# Sheet1.net
KiCad netlist of a schematic drawn in Altium Designer
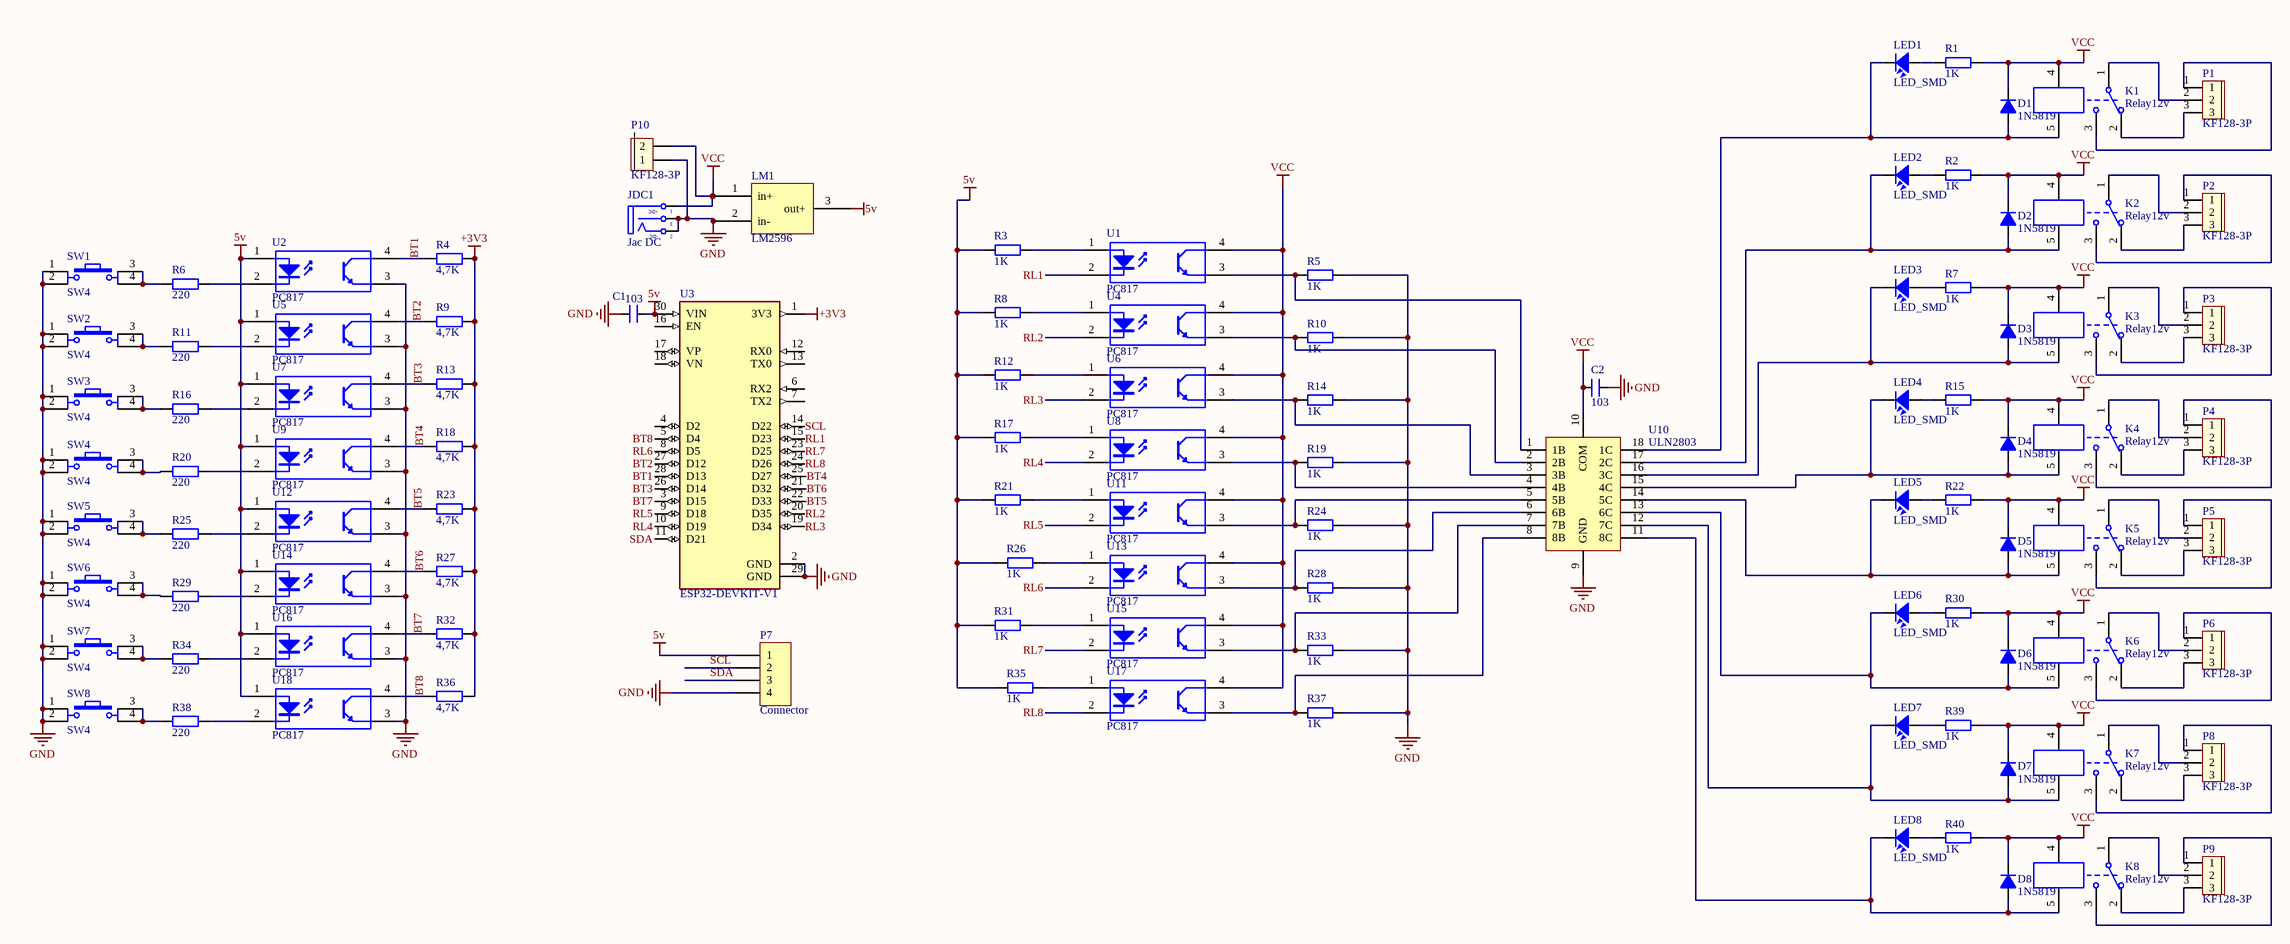
[diagram p0: Sheet1.SchDoc]

(export (version "E")
  (design (tool "Eeschema 10.0.6"))
  (components
    (comp (ref "C1")
      (value "103")
      (footprint "SM-1206")
      (description "Cap SMD")
      (libsource (lib "Schlib1") (part "CM"))
    )
    (comp (ref "C2")
      (value "103")
      (footprint "SM-1206")
      (description "Cap SMD")
      (libsource (lib "Schlib1") (part "CM"))
    )
    (comp (ref "D1") (value "1N5819") (footprint "diot_smd") (libsource (lib "Schlib1") (part "1N5819")))
    (comp (ref "D2") (value "1N5819") (footprint "diot_smd") (libsource (lib "Schlib1") (part "1N5819")))
    (comp (ref "D3") (value "1N5819") (footprint "diot_smd") (libsource (lib "Schlib1") (part "1N5819")))
    (comp (ref "D4") (value "1N5819") (footprint "diot_smd") (libsource (lib "Schlib1") (part "1N5819")))
    (comp (ref "D5") (value "1N5819") (footprint "diot_smd") (libsource (lib "Schlib1") (part "1N5819")))
    (comp (ref "D6") (value "1N5819") (footprint "diot_smd") (libsource (lib "Schlib1") (part "1N5819")))
    (comp (ref "D7") (value "1N5819") (footprint "diot_smd") (libsource (lib "Schlib1") (part "1N5819")))
    (comp (ref "D8") (value "1N5819") (footprint "diot_smd") (libsource (lib "Schlib1") (part "1N5819")))
    (comp (ref "JDC1")
      (value "Jac DC")
      (footprint "DC-IN")
      (description "Jac DC input")
      (libsource (lib "Schlib1") (part "DCIN"))
    )
    (comp (ref "K1")
      (value "Relay12v")
      (footprint "RELAY-10A5pin")
      (description "SRD-05VDC-SL-C1")
      (fields (field (name "PUBLISHER") "Altium Limited"))
      (libsource (lib "Schlib1") (part "Relay-SRD-05VDC-SL-C1"))
    )
    (comp (ref "K2")
      (value "Relay12v")
      (footprint "RELAY-10A5pin")
      (description "SRD-05VDC-SL-C1")
      (fields (field (name "PUBLISHER") "Altium Limited"))
      (libsource (lib "Schlib1") (part "Relay-SRD-05VDC-SL-C1"))
    )
    (comp (ref "K3")
      (value "Relay12v")
      (footprint "RELAY-10A5pin")
      (description "SRD-05VDC-SL-C1")
      (fields (field (name "PUBLISHER") "Altium Limited"))
      (libsource (lib "Schlib1") (part "Relay-SRD-05VDC-SL-C1"))
    )
    (comp (ref "K4")
      (value "Relay12v")
      (footprint "RELAY-10A5pin")
      (description "SRD-05VDC-SL-C1")
      (fields (field (name "PUBLISHER") "Altium Limited"))
      (libsource (lib "Schlib1") (part "Relay-SRD-05VDC-SL-C1"))
    )
    (comp (ref "K5")
      (value "Relay12v")
      (footprint "RELAY-10A5pin")
      (description "SRD-05VDC-SL-C1")
      (fields (field (name "PUBLISHER") "Altium Limited"))
      (libsource (lib "Schlib1") (part "Relay-SRD-05VDC-SL-C1"))
    )
    (comp (ref "K6")
      (value "Relay12v")
      (footprint "RELAY-10A5pin")
      (description "SRD-05VDC-SL-C1")
      (fields (field (name "PUBLISHER") "Altium Limited"))
      (libsource (lib "Schlib1") (part "Relay-SRD-05VDC-SL-C1"))
    )
    (comp (ref "K7")
      (value "Relay12v")
      (footprint "RELAY-10A5pin")
      (description "SRD-05VDC-SL-C1")
      (fields (field (name "PUBLISHER") "Altium Limited"))
      (libsource (lib "Schlib1") (part "Relay-SRD-05VDC-SL-C1"))
    )
    (comp (ref "K8")
      (value "Relay12v")
      (footprint "RELAY-10A5pin")
      (description "SRD-05VDC-SL-C1")
      (fields (field (name "PUBLISHER") "Altium Limited"))
      (libsource (lib "Schlib1") (part "Relay-SRD-05VDC-SL-C1"))
    )
    (comp (ref "LED1")
      (value "LED_SMD")
      (footprint "SM-LED-GEEN 1206")
      (libsource (lib "Schlib1") (part "LED_SMD"))
    )
    (comp (ref "LED2")
      (value "LED_SMD")
      (footprint "SM-LED-GEEN 1206")
      (libsource (lib "Schlib1") (part "LED_SMD"))
    )
    (comp (ref "LED3")
      (value "LED_SMD")
      (footprint "SM-LED-GEEN 1206")
      (libsource (lib "Schlib1") (part "LED_SMD"))
    )
    (comp (ref "LED4")
      (value "LED_SMD")
      (footprint "SM-LED-GEEN 1206")
      (libsource (lib "Schlib1") (part "LED_SMD"))
    )
    (comp (ref "LED5")
      (value "LED_SMD")
      (footprint "SM-LED-GEEN 1206")
      (libsource (lib "Schlib1") (part "LED_SMD"))
    )
    (comp (ref "LED6")
      (value "LED_SMD")
      (footprint "SM-LED-GEEN 1206")
      (libsource (lib "Schlib1") (part "LED_SMD"))
    )
    (comp (ref "LED7")
      (value "LED_SMD")
      (footprint "SM-LED-GEEN 1206")
      (libsource (lib "Schlib1") (part "LED_SMD"))
    )
    (comp (ref "LED8")
      (value "LED_SMD")
      (footprint "SM-LED-GEEN 1206")
      (libsource (lib "Schlib1") (part "LED_SMD"))
    )
    (comp (ref "LM1")
      (value "LM2596")
      (footprint "module2596_DUNG")
      (libsource (lib "Schlib1") (part "LM2596 module_dung"))
    )
    (comp (ref "P1")
      (value "KF128-3P")
      (footprint "con 3 kf128")
      (description "Cắm")
      (libsource (lib "Schlib1") (part "Con 3 KF128"))
    )
    (comp (ref "P2")
      (value "KF128-3P")
      (footprint "con 3 kf128")
      (description "Cắm")
      (libsource (lib "Schlib1") (part "Con 3 KF128"))
    )
    (comp (ref "P3")
      (value "KF128-3P")
      (footprint "con 3 kf128")
      (description "Cắm")
      (libsource (lib "Schlib1") (part "Con 3 KF128"))
    )
    (comp (ref "P4")
      (value "KF128-3P")
      (footprint "con 3 kf128")
      (description "Cắm")
      (libsource (lib "Schlib1") (part "Con 3 KF128"))
    )
    (comp (ref "P5")
      (value "KF128-3P")
      (footprint "con 3 kf128")
      (description "Cắm")
      (libsource (lib "Schlib1") (part "Con 3 KF128"))
    )
    (comp (ref "P6")
      (value "KF128-3P")
      (footprint "con 3 kf128")
      (description "Cắm")
      (libsource (lib "Schlib1") (part "Con 3 KF128"))
    )
    (comp (ref "P7")
      (value "Connector")
      (footprint "JST-XH_B4B-XH-A")
      (libsource (lib "Schlib1") (part "Connector_4pin"))
    )
    (comp (ref "P8")
      (value "KF128-3P")
      (footprint "con 3 kf128")
      (description "Cắm")
      (libsource (lib "Schlib1") (part "Con 3 KF128"))
    )
    (comp (ref "P9")
      (value "KF128-3P")
      (footprint "con 3 kf128")
      (description "Cắm")
      (libsource (lib "Schlib1") (part "Con 3 KF128"))
    )
    (comp (ref "P10")
      (value "KF128-3P")
      (footprint "con 2 kf128")
      (description "Cắm")
      (libsource (lib "Schlib1") (part "Con 2 KF128"))
    )
    (comp (ref "R1")
      (value "1K")
      (footprint "SM-1206")
      (description "Resistor SMD")
      (libsource (lib "Schlib1") (part "RM"))
    )
    (comp (ref "R2")
      (value "1K")
      (footprint "SM-1206")
      (description "Resistor SMD")
      (libsource (lib "Schlib1") (part "RM"))
    )
    (comp (ref "R3")
      (value "1K")
      (footprint "SM-1206")
      (description "Resistor SMD")
      (libsource (lib "Schlib1") (part "RM"))
    )
    (comp (ref "R4")
      (value "4,7K")
      (footprint "SM-1206")
      (description "Resistor SMD")
      (libsource (lib "Schlib1") (part "RM"))
    )
    (comp (ref "R5")
      (value "1K")
      (footprint "SM-1206")
      (description "Resistor SMD")
      (libsource (lib "Schlib1") (part "RM"))
    )
    (comp (ref "R6")
      (value "220")
      (footprint "SM-1206")
      (description "Resistor SMD")
      (libsource (lib "Schlib1") (part "RM"))
    )
    (comp (ref "R7")
      (value "1K")
      (footprint "SM-1206")
      (description "Resistor SMD")
      (libsource (lib "Schlib1") (part "RM"))
    )
    (comp (ref "R8")
      (value "1K")
      (footprint "SM-1206")
      (description "Resistor SMD")
      (libsource (lib "Schlib1") (part "RM"))
    )
    (comp (ref "R9")
      (value "4,7K")
      (footprint "SM-1206")
      (description "Resistor SMD")
      (libsource (lib "Schlib1") (part "RM"))
    )
    (comp (ref "R10")
      (value "1K")
      (footprint "SM-1206")
      (description "Resistor SMD")
      (libsource (lib "Schlib1") (part "RM"))
    )
    (comp (ref "R11")
      (value "220")
      (footprint "SM-1206")
      (description "Resistor SMD")
      (libsource (lib "Schlib1") (part "RM"))
    )
    (comp (ref "R12")
      (value "1K")
      (footprint "SM-1206")
      (description "Resistor SMD")
      (libsource (lib "Schlib1") (part "RM"))
    )
    (comp (ref "R13")
      (value "4,7K")
      (footprint "SM-1206")
      (description "Resistor SMD")
      (libsource (lib "Schlib1") (part "RM"))
    )
    (comp (ref "R14")
      (value "1K")
      (footprint "SM-1206")
      (description "Resistor SMD")
      (libsource (lib "Schlib1") (part "RM"))
    )
    (comp (ref "R15")
      (value "1K")
      (footprint "SM-1206")
      (description "Resistor SMD")
      (libsource (lib "Schlib1") (part "RM"))
    )
    (comp (ref "R16")
      (value "220")
      (footprint "SM-1206")
      (description "Resistor SMD")
      (libsource (lib "Schlib1") (part "RM"))
    )
    (comp (ref "R17")
      (value "1K")
      (footprint "SM-1206")
      (description "Resistor SMD")
      (libsource (lib "Schlib1") (part "RM"))
    )
    (comp (ref "R18")
      (value "4,7K")
      (footprint "SM-1206")
      (description "Resistor SMD")
      (libsource (lib "Schlib1") (part "RM"))
    )
    (comp (ref "R19")
      (value "1K")
      (footprint "SM-1206")
      (description "Resistor SMD")
      (libsource (lib "Schlib1") (part "RM"))
    )
    (comp (ref "R20")
      (value "220")
      (footprint "SM-1206")
      (description "Resistor SMD")
      (libsource (lib "Schlib1") (part "RM"))
    )
    (comp (ref "R21")
      (value "1K")
      (footprint "SM-1206")
      (description "Resistor SMD")
      (libsource (lib "Schlib1") (part "RM"))
    )
    (comp (ref "R22")
      (value "1K")
      (footprint "SM-1206")
      (description "Resistor SMD")
      (libsource (lib "Schlib1") (part "RM"))
    )
    (comp (ref "R23")
      (value "4,7K")
      (footprint "SM-1206")
      (description "Resistor SMD")
      (libsource (lib "Schlib1") (part "RM"))
    )
    (comp (ref "R24")
      (value "1K")
      (footprint "SM-1206")
      (description "Resistor SMD")
      (libsource (lib "Schlib1") (part "RM"))
    )
    (comp (ref "R25")
      (value "220")
      (footprint "SM-1206")
      (description "Resistor SMD")
      (libsource (lib "Schlib1") (part "RM"))
    )
    (comp (ref "R26")
      (value "1K")
      (footprint "SM-1206")
      (description "Resistor SMD")
      (libsource (lib "Schlib1") (part "RM"))
    )
    (comp (ref "R27")
      (value "4,7K")
      (footprint "SM-1206")
      (description "Resistor SMD")
      (libsource (lib "Schlib1") (part "RM"))
    )
    (comp (ref "R28")
      (value "1K")
      (footprint "SM-1206")
      (description "Resistor SMD")
      (libsource (lib "Schlib1") (part "RM"))
    )
    (comp (ref "R29")
      (value "220")
      (footprint "SM-1206")
      (description "Resistor SMD")
      (libsource (lib "Schlib1") (part "RM"))
    )
    (comp (ref "R30")
      (value "1K")
      (footprint "SM-1206")
      (description "Resistor SMD")
      (libsource (lib "Schlib1") (part "RM"))
    )
    (comp (ref "R31")
      (value "1K")
      (footprint "SM-1206")
      (description "Resistor SMD")
      (libsource (lib "Schlib1") (part "RM"))
    )
    (comp (ref "R32")
      (value "4,7K")
      (footprint "SM-1206")
      (description "Resistor SMD")
      (libsource (lib "Schlib1") (part "RM"))
    )
    (comp (ref "R33")
      (value "1K")
      (footprint "SM-1206")
      (description "Resistor SMD")
      (libsource (lib "Schlib1") (part "RM"))
    )
    (comp (ref "R34")
      (value "220")
      (footprint "SM-1206")
      (description "Resistor SMD")
      (libsource (lib "Schlib1") (part "RM"))
    )
    (comp (ref "R35")
      (value "1K")
      (footprint "SM-1206")
      (description "Resistor SMD")
      (libsource (lib "Schlib1") (part "RM"))
    )
    (comp (ref "R36")
      (value "4,7K")
      (footprint "SM-1206")
      (description "Resistor SMD")
      (libsource (lib "Schlib1") (part "RM"))
    )
    (comp (ref "R37")
      (value "1K")
      (footprint "SM-1206")
      (description "Resistor SMD")
      (libsource (lib "Schlib1") (part "RM"))
    )
    (comp (ref "R38")
      (value "220")
      (footprint "SM-1206")
      (description "Resistor SMD")
      (libsource (lib "Schlib1") (part "RM"))
    )
    (comp (ref "R39")
      (value "1K")
      (footprint "SM-1206")
      (description "Resistor SMD")
      (libsource (lib "Schlib1") (part "RM"))
    )
    (comp (ref "R40")
      (value "1K")
      (footprint "SM-1206")
      (description "Resistor SMD")
      (libsource (lib "Schlib1") (part "RM"))
    )
    (comp (ref "SW1")
      (value "SW4")
      (footprint "SW4")
      (description "Switch button 4 pin")
      (libsource (lib "Schlib1") (part "SW4"))
    )
    (comp (ref "SW2")
      (value "SW4")
      (footprint "SW4")
      (description "Switch button 4 pin")
      (libsource (lib "Schlib1") (part "SW4"))
    )
    (comp (ref "SW3")
      (value "SW4")
      (footprint "SW4")
      (description "Switch button 4 pin")
      (libsource (lib "Schlib1") (part "SW4"))
    )
    (comp (ref "SW4")
      (value "SW4")
      (footprint "SW4")
      (description "Switch button 4 pin")
      (libsource (lib "Schlib1") (part "SW4"))
    )
    (comp (ref "SW5")
      (value "SW4")
      (footprint "SW4")
      (description "Switch button 4 pin")
      (libsource (lib "Schlib1") (part "SW4"))
    )
    (comp (ref "SW6")
      (value "SW4")
      (footprint "SW4")
      (description "Switch button 4 pin")
      (libsource (lib "Schlib1") (part "SW4"))
    )
    (comp (ref "SW7")
      (value "SW4")
      (footprint "SW4")
      (description "Switch button 4 pin")
      (libsource (lib "Schlib1") (part "SW4"))
    )
    (comp (ref "SW8")
      (value "SW4")
      (footprint "SW4")
      (description "Switch button 4 pin")
      (libsource (lib "Schlib1") (part "SW4"))
    )
    (comp (ref "U1")
      (value "PC817")
      (footprint "PhotoCoupler_SMD")
      (description "4-Pin Phototransistor Optocoupler")
      (fields (field (name "PUBLISHER") "Altium Limited"))
      (libsource (lib "Schlib1") (part "PC817"))
    )
    (comp (ref "U2")
      (value "PC817")
      (footprint "PhotoCoupler_SMD")
      (description "4-Pin Phototransistor Optocoupler")
      (fields (field (name "PUBLISHER") "Altium Limited"))
      (libsource (lib "Schlib1") (part "PC817"))
    )
    (comp (ref "U3")
      (value "ESP32-DEVKIT-V1")
      (footprint "MODULE_ESP32_DEVKIT_V1")
      (fields (field (name "MF") "Do it"))
      (libsource (lib "Schlib1") (part "ESP32-DEVKIT-V1"))
    )
    (comp (ref "U4")
      (value "PC817")
      (footprint "PhotoCoupler_SMD")
      (description "4-Pin Phototransistor Optocoupler")
      (fields (field (name "PUBLISHER") "Altium Limited"))
      (libsource (lib "Schlib1") (part "PC817"))
    )
    (comp (ref "U5")
      (value "PC817")
      (footprint "PhotoCoupler_SMD")
      (description "4-Pin Phototransistor Optocoupler")
      (fields (field (name "PUBLISHER") "Altium Limited"))
      (libsource (lib "Schlib1") (part "PC817"))
    )
    (comp (ref "U6")
      (value "PC817")
      (footprint "PhotoCoupler_SMD")
      (description "4-Pin Phototransistor Optocoupler")
      (fields (field (name "PUBLISHER") "Altium Limited"))
      (libsource (lib "Schlib1") (part "PC817"))
    )
    (comp (ref "U7")
      (value "PC817")
      (footprint "PhotoCoupler_SMD")
      (description "4-Pin Phototransistor Optocoupler")
      (fields (field (name "PUBLISHER") "Altium Limited"))
      (libsource (lib "Schlib1") (part "PC817"))
    )
    (comp (ref "U8")
      (value "PC817")
      (footprint "PhotoCoupler_SMD")
      (description "4-Pin Phototransistor Optocoupler")
      (fields (field (name "PUBLISHER") "Altium Limited"))
      (libsource (lib "Schlib1") (part "PC817"))
    )
    (comp (ref "U9")
      (value "PC817")
      (footprint "PhotoCoupler_SMD")
      (description "4-Pin Phototransistor Optocoupler")
      (fields (field (name "PUBLISHER") "Altium Limited"))
      (libsource (lib "Schlib1") (part "PC817"))
    )
    (comp (ref "U10")
      (value "ULN2803")
      (footprint "SO-18")
      (description "ULN2803A Darlington Transistor Arrays")
      (libsource (lib "Schlib1") (part "ULN2803"))
    )
    (comp (ref "U11")
      (value "PC817")
      (footprint "PhotoCoupler_SMD")
      (description "4-Pin Phototransistor Optocoupler")
      (fields (field (name "PUBLISHER") "Altium Limited"))
      (libsource (lib "Schlib1") (part "PC817"))
    )
    (comp (ref "U12")
      (value "PC817")
      (footprint "PhotoCoupler_SMD")
      (description "4-Pin Phototransistor Optocoupler")
      (fields (field (name "PUBLISHER") "Altium Limited"))
      (libsource (lib "Schlib1") (part "PC817"))
    )
    (comp (ref "U13")
      (value "PC817")
      (footprint "PhotoCoupler_SMD")
      (description "4-Pin Phototransistor Optocoupler")
      (fields (field (name "PUBLISHER") "Altium Limited"))
      (libsource (lib "Schlib1") (part "PC817"))
    )
    (comp (ref "U14")
      (value "PC817")
      (footprint "PhotoCoupler_SMD")
      (description "4-Pin Phototransistor Optocoupler")
      (fields (field (name "PUBLISHER") "Altium Limited"))
      (libsource (lib "Schlib1") (part "PC817"))
    )
    (comp (ref "U15")
      (value "PC817")
      (footprint "PhotoCoupler_SMD")
      (description "4-Pin Phototransistor Optocoupler")
      (fields (field (name "PUBLISHER") "Altium Limited"))
      (libsource (lib "Schlib1") (part "PC817"))
    )
    (comp (ref "U16")
      (value "PC817")
      (footprint "PhotoCoupler_SMD")
      (description "4-Pin Phototransistor Optocoupler")
      (fields (field (name "PUBLISHER") "Altium Limited"))
      (libsource (lib "Schlib1") (part "PC817"))
    )
    (comp (ref "U17")
      (value "PC817")
      (footprint "PhotoCoupler_SMD")
      (description "4-Pin Phototransistor Optocoupler")
      (fields (field (name "PUBLISHER") "Altium Limited"))
      (libsource (lib "Schlib1") (part "PC817"))
    )
    (comp (ref "U18")
      (value "PC817")
      (footprint "PhotoCoupler_SMD")
      (description "4-Pin Phototransistor Optocoupler")
      (fields (field (name "PUBLISHER") "Altium Limited"))
      (libsource (lib "Schlib1") (part "PC817"))
    )
  )
  (nets
    (net (code "1") (name "+3V3") (class "Default")
      (node (ref "R13") (pin "2") (pinfunction "2_2") (pintype "passive"))
      (node (ref "R18") (pin "2") (pinfunction "2_2") (pintype "passive"))
      (node (ref "R23") (pin "2") (pinfunction "2_2") (pintype "passive"))
      (node (ref "R27") (pin "2") (pinfunction "2_2") (pintype "passive"))
      (node (ref "R32") (pin "2") (pinfunction "2_2") (pintype "passive"))
      (node (ref "R36") (pin "2") (pinfunction "2_2") (pintype "passive"))
      (node (ref "R4") (pin "2") (pinfunction "2_2") (pintype "passive"))
      (node (ref "R9") (pin "2") (pinfunction "2_2") (pintype "passive"))
      (node (ref "U3") (pin "1") (pinfunction "3V3_1") (pintype "output"))
    )
    (net (code "2") (name "/BT1") (class "Default")
      (node (ref "R4") (pin "1") (pinfunction "1_1") (pintype "passive"))
      (node (ref "U2") (pin "4") (pinfunction "C_4") (pintype "passive"))
      (node (ref "U3") (pin "28") (pinfunction "D13_28") (pintype "bidirectional"))
    )
    (net (code "3") (name "/BT2") (class "Default")
      (node (ref "R9") (pin "1") (pinfunction "1_1") (pintype "passive"))
      (node (ref "U3") (pin "27") (pinfunction "D12_27") (pintype "bidirectional"))
      (node (ref "U5") (pin "4") (pinfunction "C_4") (pintype "passive"))
    )
    (net (code "4") (name "/BT3") (class "Default")
      (node (ref "R13") (pin "1") (pinfunction "1_1") (pintype "passive"))
      (node (ref "U3") (pin "26") (pinfunction "D14_26") (pintype "bidirectional"))
      (node (ref "U7") (pin "4") (pinfunction "C_4") (pintype "passive"))
    )
    (net (code "5") (name "/BT4") (class "Default")
      (node (ref "R18") (pin "1") (pinfunction "1_1") (pintype "passive"))
      (node (ref "U3") (pin "25") (pinfunction "D27_25") (pintype "bidirectional"))
      (node (ref "U9") (pin "4") (pinfunction "C_4") (pintype "passive"))
    )
    (net (code "6") (name "/BT5") (class "Default")
      (node (ref "R23") (pin "1") (pinfunction "1_1") (pintype "passive"))
      (node (ref "U12") (pin "4") (pinfunction "C_4") (pintype "passive"))
      (node (ref "U3") (pin "22") (pinfunction "D33_22") (pintype "bidirectional"))
    )
    (net (code "7") (name "/BT6") (class "Default")
      (node (ref "R27") (pin "1") (pinfunction "1_1") (pintype "passive"))
      (node (ref "U14") (pin "4") (pinfunction "C_4") (pintype "passive"))
      (node (ref "U3") (pin "21") (pinfunction "D32_21") (pintype "bidirectional"))
    )
    (net (code "8") (name "/BT7") (class "Default")
      (node (ref "R32") (pin "1") (pinfunction "1_1") (pintype "passive"))
      (node (ref "U16") (pin "4") (pinfunction "C_4") (pintype "passive"))
      (node (ref "U3") (pin "3") (pinfunction "D15_3") (pintype "bidirectional"))
    )
    (net (code "9") (name "/BT8") (class "Default")
      (node (ref "R36") (pin "1") (pinfunction "1_1") (pintype "passive"))
      (node (ref "U18") (pin "4") (pinfunction "C_4") (pintype "passive"))
      (node (ref "U3") (pin "5") (pinfunction "D4_5") (pintype "bidirectional"))
    )
    (net (code "10") (name "/RL1") (class "Default")
      (node (ref "U1") (pin "2") (pinfunction "K_2") (pintype "passive"))
      (node (ref "U3") (pin "15") (pinfunction "D23_15") (pintype "bidirectional"))
    )
    (net (code "11") (name "/RL2") (class "Default")
      (node (ref "U3") (pin "20") (pinfunction "D35_20") (pintype "bidirectional"))
      (node (ref "U4") (pin "2") (pinfunction "K_2") (pintype "passive"))
    )
    (net (code "12") (name "/RL3") (class "Default")
      (node (ref "U3") (pin "19") (pinfunction "D34_19") (pintype "bidirectional"))
      (node (ref "U6") (pin "2") (pinfunction "K_2") (pintype "passive"))
    )
    (net (code "13") (name "/RL4") (class "Default")
      (node (ref "U3") (pin "10") (pinfunction "D19_10") (pintype "bidirectional"))
      (node (ref "U8") (pin "2") (pinfunction "K_2") (pintype "passive"))
    )
    (net (code "14") (name "/RL5") (class "Default")
      (node (ref "U11") (pin "2") (pinfunction "K_2") (pintype "passive"))
      (node (ref "U3") (pin "9") (pinfunction "D18_9") (pintype "bidirectional"))
    )
    (net (code "15") (name "/RL6") (class "Default")
      (node (ref "U13") (pin "2") (pinfunction "K_2") (pintype "passive"))
      (node (ref "U3") (pin "8") (pinfunction "D5_8") (pintype "bidirectional"))
    )
    (net (code "16") (name "/RL7") (class "Default")
      (node (ref "U15") (pin "2") (pinfunction "K_2") (pintype "passive"))
      (node (ref "U3") (pin "23") (pinfunction "D25_23") (pintype "bidirectional"))
    )
    (net (code "17") (name "/RL8") (class "Default")
      (node (ref "U17") (pin "2") (pinfunction "K_2") (pintype "passive"))
      (node (ref "U3") (pin "24") (pinfunction "D26_24") (pintype "bidirectional"))
    )
    (net (code "18") (name "/SCL") (class "Default")
      (node (ref "P7") (pin "2") (pinfunction "2_2") (pintype "passive"))
      (node (ref "U3") (pin "14") (pinfunction "D22_14") (pintype "bidirectional"))
    )
    (net (code "19") (name "/SDA") (class "Default")
      (node (ref "P7") (pin "3") (pinfunction "3_3") (pintype "passive"))
      (node (ref "U3") (pin "11") (pinfunction "D21_11") (pintype "bidirectional"))
    )
    (net (code "20") (name "5v") (class "Default")
      (node (ref "C1") (pin "1") (pinfunction "1_1") (pintype "passive"))
      (node (ref "LM1") (pin "3") (pinfunction "out+_3") (pintype "passive"))
      (node (ref "P7") (pin "1") (pinfunction "1_1") (pintype "passive"))
      (node (ref "R12") (pin "1") (pinfunction "1_1") (pintype "passive"))
      (node (ref "R17") (pin "1") (pinfunction "1_1") (pintype "passive"))
      (node (ref "R21") (pin "1") (pinfunction "1_1") (pintype "passive"))
      (node (ref "R26") (pin "1") (pinfunction "1_1") (pintype "passive"))
      (node (ref "R3") (pin "1") (pinfunction "1_1") (pintype "passive"))
      (node (ref "R31") (pin "1") (pinfunction "1_1") (pintype "passive"))
      (node (ref "R35") (pin "1") (pinfunction "1_1") (pintype "passive"))
      (node (ref "R8") (pin "1") (pinfunction "1_1") (pintype "passive"))
      (node (ref "U12") (pin "1") (pinfunction "A_1") (pintype "passive"))
      (node (ref "U14") (pin "1") (pinfunction "A_1") (pintype "passive"))
      (node (ref "U16") (pin "1") (pinfunction "A_1") (pintype "passive"))
      (node (ref "U18") (pin "1") (pinfunction "A_1") (pintype "passive"))
      (node (ref "U2") (pin "1") (pinfunction "A_1") (pintype "passive"))
      (node (ref "U3") (pin "30") (pinfunction "VIN_30") (pintype "input"))
      (node (ref "U5") (pin "1") (pinfunction "A_1") (pintype "passive"))
      (node (ref "U7") (pin "1") (pinfunction "A_1") (pintype "passive"))
      (node (ref "U9") (pin "1") (pinfunction "A_1") (pintype "passive"))
    )
    (net (code "21") (name "GND") (class "Default")
      (node (ref "C1") (pin "2") (pinfunction "2_2") (pintype "passive"))
      (node (ref "C2") (pin "1") (pinfunction "1_1") (pintype "passive"))
      (node (ref "JDC1") (pin "2") (pinfunction "TN_2") (pintype "passive"))
      (node (ref "JDC1") (pin "3") (pinfunction "S_3") (pintype "power_in"))
      (node (ref "LM1") (pin "2") (pinfunction "in-_2") (pintype "passive"))
      (node (ref "P10") (pin "1") (pinfunction "1_1") (pintype "passive"))
      (node (ref "P7") (pin "4") (pinfunction "4_4") (pintype "passive"))
      (node (ref "R10") (pin "2") (pinfunction "2_2") (pintype "passive"))
      (node (ref "R14") (pin "2") (pinfunction "2_2") (pintype "passive"))
      (node (ref "R19") (pin "2") (pinfunction "2_2") (pintype "passive"))
      (node (ref "R24") (pin "2") (pinfunction "2_2") (pintype "passive"))
      (node (ref "R28") (pin "2") (pinfunction "2_2") (pintype "passive"))
      (node (ref "R33") (pin "2") (pinfunction "2_2") (pintype "passive"))
      (node (ref "R37") (pin "2") (pinfunction "2_2") (pintype "passive"))
      (node (ref "R5") (pin "2") (pinfunction "2_2") (pintype "passive"))
      (node (ref "SW1") (pin "1") (pintype "passive"))
      (node (ref "SW1") (pin "2") (pintype "passive"))
      (node (ref "SW2") (pin "1") (pintype "passive"))
      (node (ref "SW2") (pin "2") (pintype "passive"))
      (node (ref "SW3") (pin "1") (pintype "passive"))
      (node (ref "SW3") (pin "2") (pintype "passive"))
      (node (ref "SW4") (pin "1") (pintype "passive"))
      (node (ref "SW4") (pin "2") (pintype "passive"))
      (node (ref "SW5") (pin "1") (pintype "passive"))
      (node (ref "SW5") (pin "2") (pintype "passive"))
      (node (ref "SW6") (pin "1") (pintype "passive"))
      (node (ref "SW6") (pin "2") (pintype "passive"))
      (node (ref "SW7") (pin "1") (pintype "passive"))
      (node (ref "SW7") (pin "2") (pintype "passive"))
      (node (ref "SW8") (pin "1") (pintype "passive"))
      (node (ref "SW8") (pin "2") (pintype "passive"))
      (node (ref "U10") (pin "9") (pinfunction "GND_9") (pintype "passive"))
      (node (ref "U12") (pin "3") (pinfunction "E_3") (pintype "passive"))
      (node (ref "U14") (pin "3") (pinfunction "E_3") (pintype "passive"))
      (node (ref "U16") (pin "3") (pinfunction "E_3") (pintype "passive"))
      (node (ref "U18") (pin "3") (pinfunction "E_3") (pintype "passive"))
      (node (ref "U2") (pin "3") (pinfunction "E_3") (pintype "passive"))
      (node (ref "U3") (pin "2") (pinfunction "GND_2") (pintype "power_in"))
      (node (ref "U3") (pin "29") (pinfunction "GND_29") (pintype "power_in"))
      (node (ref "U5") (pin "3") (pinfunction "E_3") (pintype "passive"))
      (node (ref "U7") (pin "3") (pinfunction "E_3") (pintype "passive"))
      (node (ref "U9") (pin "3") (pinfunction "E_3") (pintype "passive"))
    )
    (net (code "22") (name "Net-(D1-A)") (class "Default")
      (node (ref "D1") (pin "1") (pinfunction "A_1") (pintype "passive"))
      (node (ref "K1") (pin "5") (pintype "passive"))
      (node (ref "LED1") (pin "2") (pinfunction "2_2") (pintype "passive"))
      (node (ref "U10") (pin "18") (pinfunction "1C_18") (pintype "passive"))
    )
    (net (code "23") (name "Net-(D2-A)") (class "Default")
      (node (ref "D2") (pin "1") (pinfunction "A_1") (pintype "passive"))
      (node (ref "K2") (pin "5") (pintype "passive"))
      (node (ref "LED2") (pin "2") (pinfunction "2_2") (pintype "passive"))
      (node (ref "U10") (pin "17") (pinfunction "2C_17") (pintype "passive"))
    )
    (net (code "24") (name "Net-(D3-A)") (class "Default")
      (node (ref "D3") (pin "1") (pinfunction "A_1") (pintype "passive"))
      (node (ref "K3") (pin "5") (pintype "passive"))
      (node (ref "LED3") (pin "2") (pinfunction "2_2") (pintype "passive"))
      (node (ref "U10") (pin "16") (pinfunction "3C_16") (pintype "passive"))
    )
    (net (code "25") (name "Net-(D4-A)") (class "Default")
      (node (ref "D4") (pin "1") (pinfunction "A_1") (pintype "passive"))
      (node (ref "K4") (pin "5") (pintype "passive"))
      (node (ref "LED4") (pin "2") (pinfunction "2_2") (pintype "passive"))
      (node (ref "U10") (pin "15") (pinfunction "4C_15") (pintype "passive"))
    )
    (net (code "26") (name "Net-(D5-A)") (class "Default")
      (node (ref "D5") (pin "1") (pinfunction "A_1") (pintype "passive"))
      (node (ref "K5") (pin "5") (pintype "passive"))
      (node (ref "LED5") (pin "2") (pinfunction "2_2") (pintype "passive"))
      (node (ref "U10") (pin "14") (pinfunction "5C_14") (pintype "passive"))
    )
    (net (code "27") (name "Net-(D6-A)") (class "Default")
      (node (ref "D6") (pin "1") (pinfunction "A_1") (pintype "passive"))
      (node (ref "K6") (pin "5") (pintype "passive"))
      (node (ref "LED6") (pin "2") (pinfunction "2_2") (pintype "passive"))
      (node (ref "U10") (pin "13") (pinfunction "6C_13") (pintype "passive"))
    )
    (net (code "28") (name "Net-(D7-A)") (class "Default")
      (node (ref "D7") (pin "1") (pinfunction "A_1") (pintype "passive"))
      (node (ref "K7") (pin "5") (pintype "passive"))
      (node (ref "LED7") (pin "2") (pinfunction "2_2") (pintype "passive"))
      (node (ref "U10") (pin "12") (pinfunction "7C_12") (pintype "passive"))
    )
    (net (code "29") (name "Net-(D8-A)") (class "Default")
      (node (ref "D8") (pin "1") (pinfunction "A_1") (pintype "passive"))
      (node (ref "K8") (pin "5") (pintype "passive"))
      (node (ref "LED8") (pin "2") (pinfunction "2_2") (pintype "passive"))
      (node (ref "U10") (pin "11") (pinfunction "8C_11") (pintype "passive"))
    )
    (net (code "30") (name "Net-(K1-COM)") (class "Default")
      (node (ref "K1") (pin "1") (pinfunction "COM_1") (pintype "passive"))
      (node (ref "P1") (pin "2") (pinfunction "2_2") (pintype "passive"))
    )
    (net (code "31") (name "Net-(K1-NC)") (class "Default")
      (node (ref "K1") (pin "2") (pinfunction "NC_2") (pintype "passive"))
      (node (ref "P1") (pin "3") (pinfunction "3_3") (pintype "passive"))
    )
    (net (code "32") (name "Net-(K1-NO)") (class "Default")
      (node (ref "K1") (pin "3") (pinfunction "NO_3") (pintype "passive"))
      (node (ref "P1") (pin "1") (pinfunction "1_1") (pintype "passive"))
    )
    (net (code "33") (name "Net-(K2-COM)") (class "Default")
      (node (ref "K2") (pin "1") (pinfunction "COM_1") (pintype "passive"))
      (node (ref "P2") (pin "2") (pinfunction "2_2") (pintype "passive"))
    )
    (net (code "34") (name "Net-(K2-NC)") (class "Default")
      (node (ref "K2") (pin "2") (pinfunction "NC_2") (pintype "passive"))
      (node (ref "P2") (pin "3") (pinfunction "3_3") (pintype "passive"))
    )
    (net (code "35") (name "Net-(K2-NO)") (class "Default")
      (node (ref "K2") (pin "3") (pinfunction "NO_3") (pintype "passive"))
      (node (ref "P2") (pin "1") (pinfunction "1_1") (pintype "passive"))
    )
    (net (code "36") (name "Net-(K3-COM)") (class "Default")
      (node (ref "K3") (pin "1") (pinfunction "COM_1") (pintype "passive"))
      (node (ref "P3") (pin "2") (pinfunction "2_2") (pintype "passive"))
    )
    (net (code "37") (name "Net-(K3-NC)") (class "Default")
      (node (ref "K3") (pin "2") (pinfunction "NC_2") (pintype "passive"))
      (node (ref "P3") (pin "3") (pinfunction "3_3") (pintype "passive"))
    )
    (net (code "38") (name "Net-(K3-NO)") (class "Default")
      (node (ref "K3") (pin "3") (pinfunction "NO_3") (pintype "passive"))
      (node (ref "P3") (pin "1") (pinfunction "1_1") (pintype "passive"))
    )
    (net (code "39") (name "Net-(K4-COM)") (class "Default")
      (node (ref "K4") (pin "1") (pinfunction "COM_1") (pintype "passive"))
      (node (ref "P4") (pin "2") (pinfunction "2_2") (pintype "passive"))
    )
    (net (code "40") (name "Net-(K4-NC)") (class "Default")
      (node (ref "K4") (pin "2") (pinfunction "NC_2") (pintype "passive"))
      (node (ref "P4") (pin "3") (pinfunction "3_3") (pintype "passive"))
    )
    (net (code "41") (name "Net-(K4-NO)") (class "Default")
      (node (ref "K4") (pin "3") (pinfunction "NO_3") (pintype "passive"))
      (node (ref "P4") (pin "1") (pinfunction "1_1") (pintype "passive"))
    )
    (net (code "42") (name "Net-(K5-COM)") (class "Default")
      (node (ref "K5") (pin "1") (pinfunction "COM_1") (pintype "passive"))
      (node (ref "P5") (pin "2") (pinfunction "2_2") (pintype "passive"))
    )
    (net (code "43") (name "Net-(K5-NC)") (class "Default")
      (node (ref "K5") (pin "2") (pinfunction "NC_2") (pintype "passive"))
      (node (ref "P5") (pin "3") (pinfunction "3_3") (pintype "passive"))
    )
    (net (code "44") (name "Net-(K5-NO)") (class "Default")
      (node (ref "K5") (pin "3") (pinfunction "NO_3") (pintype "passive"))
      (node (ref "P5") (pin "1") (pinfunction "1_1") (pintype "passive"))
    )
    (net (code "45") (name "Net-(K6-COM)") (class "Default")
      (node (ref "K6") (pin "1") (pinfunction "COM_1") (pintype "passive"))
      (node (ref "P6") (pin "2") (pinfunction "2_2") (pintype "passive"))
    )
    (net (code "46") (name "Net-(K6-NC)") (class "Default")
      (node (ref "K6") (pin "2") (pinfunction "NC_2") (pintype "passive"))
      (node (ref "P6") (pin "3") (pinfunction "3_3") (pintype "passive"))
    )
    (net (code "47") (name "Net-(K6-NO)") (class "Default")
      (node (ref "K6") (pin "3") (pinfunction "NO_3") (pintype "passive"))
      (node (ref "P6") (pin "1") (pinfunction "1_1") (pintype "passive"))
    )
    (net (code "48") (name "Net-(K7-COM)") (class "Default")
      (node (ref "K7") (pin "1") (pinfunction "COM_1") (pintype "passive"))
      (node (ref "P8") (pin "2") (pinfunction "2_2") (pintype "passive"))
    )
    (net (code "49") (name "Net-(K7-NC)") (class "Default")
      (node (ref "K7") (pin "2") (pinfunction "NC_2") (pintype "passive"))
      (node (ref "P8") (pin "3") (pinfunction "3_3") (pintype "passive"))
    )
    (net (code "50") (name "Net-(K7-NO)") (class "Default")
      (node (ref "K7") (pin "3") (pinfunction "NO_3") (pintype "passive"))
      (node (ref "P8") (pin "1") (pinfunction "1_1") (pintype "passive"))
    )
    (net (code "51") (name "Net-(K8-COM)") (class "Default")
      (node (ref "K8") (pin "1") (pinfunction "COM_1") (pintype "passive"))
      (node (ref "P9") (pin "2") (pinfunction "2_2") (pintype "passive"))
    )
    (net (code "52") (name "Net-(K8-NC)") (class "Default")
      (node (ref "K8") (pin "2") (pinfunction "NC_2") (pintype "passive"))
      (node (ref "P9") (pin "3") (pinfunction "3_3") (pintype "passive"))
    )
    (net (code "53") (name "Net-(K8-NO)") (class "Default")
      (node (ref "K8") (pin "3") (pinfunction "NO_3") (pintype "passive"))
      (node (ref "P9") (pin "1") (pinfunction "1_1") (pintype "passive"))
    )
    (net (code "54") (name "Net-(LED1-Pad1)") (class "Default")
      (node (ref "LED1") (pin "1") (pinfunction "1_1") (pintype "passive"))
      (node (ref "R1") (pin "1") (pinfunction "1_1") (pintype "passive"))
    )
    (net (code "55") (name "Net-(LED2-Pad1)") (class "Default")
      (node (ref "LED2") (pin "1") (pinfunction "1_1") (pintype "passive"))
      (node (ref "R2") (pin "1") (pinfunction "1_1") (pintype "passive"))
    )
    (net (code "56") (name "Net-(LED3-Pad1)") (class "Default")
      (node (ref "LED3") (pin "1") (pinfunction "1_1") (pintype "passive"))
      (node (ref "R7") (pin "1") (pinfunction "1_1") (pintype "passive"))
    )
    (net (code "57") (name "Net-(LED4-Pad1)") (class "Default")
      (node (ref "LED4") (pin "1") (pinfunction "1_1") (pintype "passive"))
      (node (ref "R15") (pin "1") (pinfunction "1_1") (pintype "passive"))
    )
    (net (code "58") (name "Net-(LED5-Pad1)") (class "Default")
      (node (ref "LED5") (pin "1") (pinfunction "1_1") (pintype "passive"))
      (node (ref "R22") (pin "1") (pinfunction "1_1") (pintype "passive"))
    )
    (net (code "59") (name "Net-(LED6-Pad1)") (class "Default")
      (node (ref "LED6") (pin "1") (pinfunction "1_1") (pintype "passive"))
      (node (ref "R30") (pin "1") (pinfunction "1_1") (pintype "passive"))
    )
    (net (code "60") (name "Net-(LED7-Pad1)") (class "Default")
      (node (ref "LED7") (pin "1") (pinfunction "1_1") (pintype "passive"))
      (node (ref "R39") (pin "1") (pinfunction "1_1") (pintype "passive"))
    )
    (net (code "61") (name "Net-(LED8-Pad1)") (class "Default")
      (node (ref "LED8") (pin "1") (pinfunction "1_1") (pintype "passive"))
      (node (ref "R40") (pin "1") (pinfunction "1_1") (pintype "passive"))
    )
    (net (code "62") (name "Net-(R6-Pad1)") (class "Default")
      (node (ref "R6") (pin "1") (pinfunction "1_1") (pintype "passive"))
      (node (ref "SW1") (pin "3") (pintype "passive"))
      (node (ref "SW1") (pin "4") (pintype "passive"))
    )
    (net (code "63") (name "Net-(R11-Pad1)") (class "Default")
      (node (ref "R11") (pin "1") (pinfunction "1_1") (pintype "passive"))
      (node (ref "SW2") (pin "3") (pintype "passive"))
      (node (ref "SW2") (pin "4") (pintype "passive"))
    )
    (net (code "64") (name "Net-(R16-Pad1)") (class "Default")
      (node (ref "R16") (pin "1") (pinfunction "1_1") (pintype "passive"))
      (node (ref "SW3") (pin "3") (pintype "passive"))
      (node (ref "SW3") (pin "4") (pintype "passive"))
    )
    (net (code "65") (name "Net-(R20-Pad1)") (class "Default")
      (node (ref "R20") (pin "1") (pinfunction "1_1") (pintype "passive"))
      (node (ref "SW4") (pin "3") (pintype "passive"))
      (node (ref "SW4") (pin "4") (pintype "passive"))
    )
    (net (code "66") (name "Net-(R25-Pad1)") (class "Default")
      (node (ref "R25") (pin "1") (pinfunction "1_1") (pintype "passive"))
      (node (ref "SW5") (pin "3") (pintype "passive"))
      (node (ref "SW5") (pin "4") (pintype "passive"))
    )
    (net (code "67") (name "Net-(R29-Pad1)") (class "Default")
      (node (ref "R29") (pin "1") (pinfunction "1_1") (pintype "passive"))
      (node (ref "SW6") (pin "3") (pintype "passive"))
      (node (ref "SW6") (pin "4") (pintype "passive"))
    )
    (net (code "68") (name "Net-(R34-Pad1)") (class "Default")
      (node (ref "R34") (pin "1") (pinfunction "1_1") (pintype "passive"))
      (node (ref "SW7") (pin "3") (pintype "passive"))
      (node (ref "SW7") (pin "4") (pintype "passive"))
    )
    (net (code "69") (name "Net-(R38-Pad1)") (class "Default")
      (node (ref "R38") (pin "1") (pinfunction "1_1") (pintype "passive"))
      (node (ref "SW8") (pin "3") (pintype "passive"))
      (node (ref "SW8") (pin "4") (pintype "passive"))
    )
    (net (code "70") (name "Net-(U1-A)") (class "Default")
      (node (ref "R3") (pin "2") (pinfunction "2_2") (pintype "passive"))
      (node (ref "U1") (pin "1") (pinfunction "A_1") (pintype "passive"))
    )
    (net (code "71") (name "Net-(U1-E)") (class "Default")
      (node (ref "R5") (pin "1") (pinfunction "1_1") (pintype "passive"))
      (node (ref "U1") (pin "3") (pinfunction "E_3") (pintype "passive"))
      (node (ref "U10") (pin "1") (pinfunction "1B_1") (pintype "passive"))
    )
    (net (code "72") (name "Net-(U2-K)") (class "Default")
      (node (ref "R6") (pin "2") (pinfunction "2_2") (pintype "passive"))
      (node (ref "U2") (pin "2") (pinfunction "K_2") (pintype "passive"))
    )
    (net (code "73") (name "Net-(U4-A)") (class "Default")
      (node (ref "R8") (pin "2") (pinfunction "2_2") (pintype "passive"))
      (node (ref "U4") (pin "1") (pinfunction "A_1") (pintype "passive"))
    )
    (net (code "74") (name "Net-(U5-K)") (class "Default")
      (node (ref "R11") (pin "2") (pinfunction "2_2") (pintype "passive"))
      (node (ref "U5") (pin "2") (pinfunction "K_2") (pintype "passive"))
    )
    (net (code "75") (name "Net-(U6-A)") (class "Default")
      (node (ref "R12") (pin "2") (pinfunction "2_2") (pintype "passive"))
      (node (ref "U6") (pin "1") (pinfunction "A_1") (pintype "passive"))
    )
    (net (code "76") (name "Net-(U7-K)") (class "Default")
      (node (ref "R16") (pin "2") (pinfunction "2_2") (pintype "passive"))
      (node (ref "U7") (pin "2") (pinfunction "K_2") (pintype "passive"))
    )
    (net (code "77") (name "Net-(U8-A)") (class "Default")
      (node (ref "R17") (pin "2") (pinfunction "2_2") (pintype "passive"))
      (node (ref "U8") (pin "1") (pinfunction "A_1") (pintype "passive"))
    )
    (net (code "78") (name "Net-(U9-K)") (class "Default")
      (node (ref "R20") (pin "2") (pinfunction "2_2") (pintype "passive"))
      (node (ref "U9") (pin "2") (pinfunction "K_2") (pintype "passive"))
    )
    (net (code "79") (name "Net-(U10-2B)") (class "Default")
      (node (ref "R10") (pin "1") (pinfunction "1_1") (pintype "passive"))
      (node (ref "U10") (pin "2") (pinfunction "2B_2") (pintype "passive"))
      (node (ref "U4") (pin "3") (pinfunction "E_3") (pintype "passive"))
    )
    (net (code "80") (name "Net-(U10-3B)") (class "Default")
      (node (ref "R14") (pin "1") (pinfunction "1_1") (pintype "passive"))
      (node (ref "U10") (pin "3") (pinfunction "3B_3") (pintype "passive"))
      (node (ref "U6") (pin "3") (pinfunction "E_3") (pintype "passive"))
    )
    (net (code "81") (name "Net-(U10-4B)") (class "Default")
      (node (ref "R19") (pin "1") (pinfunction "1_1") (pintype "passive"))
      (node (ref "U10") (pin "4") (pinfunction "4B_4") (pintype "passive"))
      (node (ref "U8") (pin "3") (pinfunction "E_3") (pintype "passive"))
    )
    (net (code "82") (name "Net-(U10-5B)") (class "Default")
      (node (ref "R24") (pin "1") (pinfunction "1_1") (pintype "passive"))
      (node (ref "U10") (pin "5") (pinfunction "5B_5") (pintype "passive"))
      (node (ref "U11") (pin "3") (pinfunction "E_3") (pintype "passive"))
    )
    (net (code "83") (name "Net-(U10-6B)") (class "Default")
      (node (ref "R28") (pin "1") (pinfunction "1_1") (pintype "passive"))
      (node (ref "U10") (pin "6") (pinfunction "6B_6") (pintype "passive"))
      (node (ref "U13") (pin "3") (pinfunction "E_3") (pintype "passive"))
    )
    (net (code "84") (name "Net-(U10-7B)") (class "Default")
      (node (ref "R33") (pin "1") (pinfunction "1_1") (pintype "passive"))
      (node (ref "U10") (pin "7") (pinfunction "7B_7") (pintype "passive"))
      (node (ref "U15") (pin "3") (pinfunction "E_3") (pintype "passive"))
    )
    (net (code "85") (name "Net-(U10-8B)") (class "Default")
      (node (ref "R37") (pin "1") (pinfunction "1_1") (pintype "passive"))
      (node (ref "U10") (pin "8") (pinfunction "8B_8") (pintype "passive"))
      (node (ref "U17") (pin "3") (pinfunction "E_3") (pintype "passive"))
    )
    (net (code "86") (name "Net-(U11-A)") (class "Default")
      (node (ref "R21") (pin "2") (pinfunction "2_2") (pintype "passive"))
      (node (ref "U11") (pin "1") (pinfunction "A_1") (pintype "passive"))
    )
    (net (code "87") (name "Net-(U12-K)") (class "Default")
      (node (ref "R25") (pin "2") (pinfunction "2_2") (pintype "passive"))
      (node (ref "U12") (pin "2") (pinfunction "K_2") (pintype "passive"))
    )
    (net (code "88") (name "Net-(U13-A)") (class "Default")
      (node (ref "R26") (pin "2") (pinfunction "2_2") (pintype "passive"))
      (node (ref "U13") (pin "1") (pinfunction "A_1") (pintype "passive"))
    )
    (net (code "89") (name "Net-(U14-K)") (class "Default")
      (node (ref "R29") (pin "2") (pinfunction "2_2") (pintype "passive"))
      (node (ref "U14") (pin "2") (pinfunction "K_2") (pintype "passive"))
    )
    (net (code "90") (name "Net-(U15-A)") (class "Default")
      (node (ref "R31") (pin "2") (pinfunction "2_2") (pintype "passive"))
      (node (ref "U15") (pin "1") (pinfunction "A_1") (pintype "passive"))
    )
    (net (code "91") (name "Net-(U16-K)") (class "Default")
      (node (ref "R34") (pin "2") (pinfunction "2_2") (pintype "passive"))
      (node (ref "U16") (pin "2") (pinfunction "K_2") (pintype "passive"))
    )
    (net (code "92") (name "Net-(U17-A)") (class "Default")
      (node (ref "R35") (pin "2") (pinfunction "2_2") (pintype "passive"))
      (node (ref "U17") (pin "1") (pinfunction "A_1") (pintype "passive"))
    )
    (net (code "93") (name "Net-(U18-K)") (class "Default")
      (node (ref "R38") (pin "2") (pinfunction "2_2") (pintype "passive"))
      (node (ref "U18") (pin "2") (pinfunction "K_2") (pintype "passive"))
    )
    (net (code "94") (name "VCC") (class "Default")
      (node (ref "C2") (pin "2") (pinfunction "2_2") (pintype "passive"))
      (node (ref "D1") (pin "2") (pinfunction "K_2") (pintype "passive"))
      (node (ref "D2") (pin "2") (pinfunction "K_2") (pintype "passive"))
      (node (ref "D3") (pin "2") (pinfunction "K_2") (pintype "passive"))
      (node (ref "D4") (pin "2") (pinfunction "K_2") (pintype "passive"))
      (node (ref "D5") (pin "2") (pinfunction "K_2") (pintype "passive"))
      (node (ref "D6") (pin "2") (pinfunction "K_2") (pintype "passive"))
      (node (ref "D7") (pin "2") (pinfunction "K_2") (pintype "passive"))
      (node (ref "D8") (pin "2") (pinfunction "K_2") (pintype "passive"))
      (node (ref "JDC1") (pin "1") (pinfunction "T_1") (pintype "passive"))
      (node (ref "K1") (pin "4") (pintype "passive"))
      (node (ref "K2") (pin "4") (pintype "passive"))
      (node (ref "K3") (pin "4") (pintype "passive"))
      (node (ref "K4") (pin "4") (pintype "passive"))
      (node (ref "K5") (pin "4") (pintype "passive"))
      (node (ref "K6") (pin "4") (pintype "passive"))
      (node (ref "K7") (pin "4") (pintype "passive"))
      (node (ref "K8") (pin "4") (pintype "passive"))
      (node (ref "LM1") (pin "1") (pinfunction "in+_1") (pintype "passive"))
      (node (ref "P10") (pin "2") (pinfunction "2_2") (pintype "passive"))
      (node (ref "R1") (pin "2") (pinfunction "2_2") (pintype "passive"))
      (node (ref "R15") (pin "2") (pinfunction "2_2") (pintype "passive"))
      (node (ref "R2") (pin "2") (pinfunction "2_2") (pintype "passive"))
      (node (ref "R22") (pin "2") (pinfunction "2_2") (pintype "passive"))
      (node (ref "R30") (pin "2") (pinfunction "2_2") (pintype "passive"))
      (node (ref "R39") (pin "2") (pinfunction "2_2") (pintype "passive"))
      (node (ref "R40") (pin "2") (pinfunction "2_2") (pintype "passive"))
      (node (ref "R7") (pin "2") (pinfunction "2_2") (pintype "passive"))
      (node (ref "U1") (pin "4") (pinfunction "C_4") (pintype "passive"))
      (node (ref "U10") (pin "10") (pinfunction "COM_10") (pintype "passive"))
      (node (ref "U11") (pin "4") (pinfunction "C_4") (pintype "passive"))
      (node (ref "U13") (pin "4") (pinfunction "C_4") (pintype "passive"))
      (node (ref "U15") (pin "4") (pinfunction "C_4") (pintype "passive"))
      (node (ref "U17") (pin "4") (pinfunction "C_4") (pintype "passive"))
      (node (ref "U4") (pin "4") (pinfunction "C_4") (pintype "passive"))
      (node (ref "U6") (pin "4") (pinfunction "C_4") (pintype "passive"))
      (node (ref "U8") (pin "4") (pinfunction "C_4") (pintype "passive"))
    )
    (net (code "95") (name "unconnected-(U3-D2-Pad4)") (class "Default")
      (node (ref "U3") (pin "4") (pinfunction "D2_4") (pintype "bidirectional"))
    )
    (net (code "96") (name "unconnected-(U3-EN-Pad16)") (class "Default")
      (node (ref "U3") (pin "16") (pinfunction "EN_16") (pintype "input"))
    )
    (net (code "97") (name "unconnected-(U3-RX0-Pad12)") (class "Default")
      (node (ref "U3") (pin "12") (pinfunction "RX0_12") (pintype "input"))
    )
    (net (code "98") (name "unconnected-(U3-RX2-Pad6)") (class "Default")
      (node (ref "U3") (pin "6") (pinfunction "RX2_6") (pintype "input"))
    )
    (net (code "99") (name "unconnected-(U3-TX0-Pad13)") (class "Default")
      (node (ref "U3") (pin "13") (pinfunction "TX0_13") (pintype "output"))
    )
    (net (code "100") (name "unconnected-(U3-TX2-Pad7)") (class "Default")
      (node (ref "U3") (pin "7") (pinfunction "TX2_7") (pintype "output"))
    )
    (net (code "101") (name "unconnected-(U3-VN-Pad18)") (class "Default")
      (node (ref "U3") (pin "18") (pinfunction "VN_18") (pintype "bidirectional"))
    )
    (net (code "102") (name "unconnected-(U3-VP-Pad17)") (class "Default")
      (node (ref "U3") (pin "17") (pinfunction "VP_17") (pintype "bidirectional"))
    )
  )
)
